# 02.net
KiCad netlist of a schematic drawn in Altium Designer
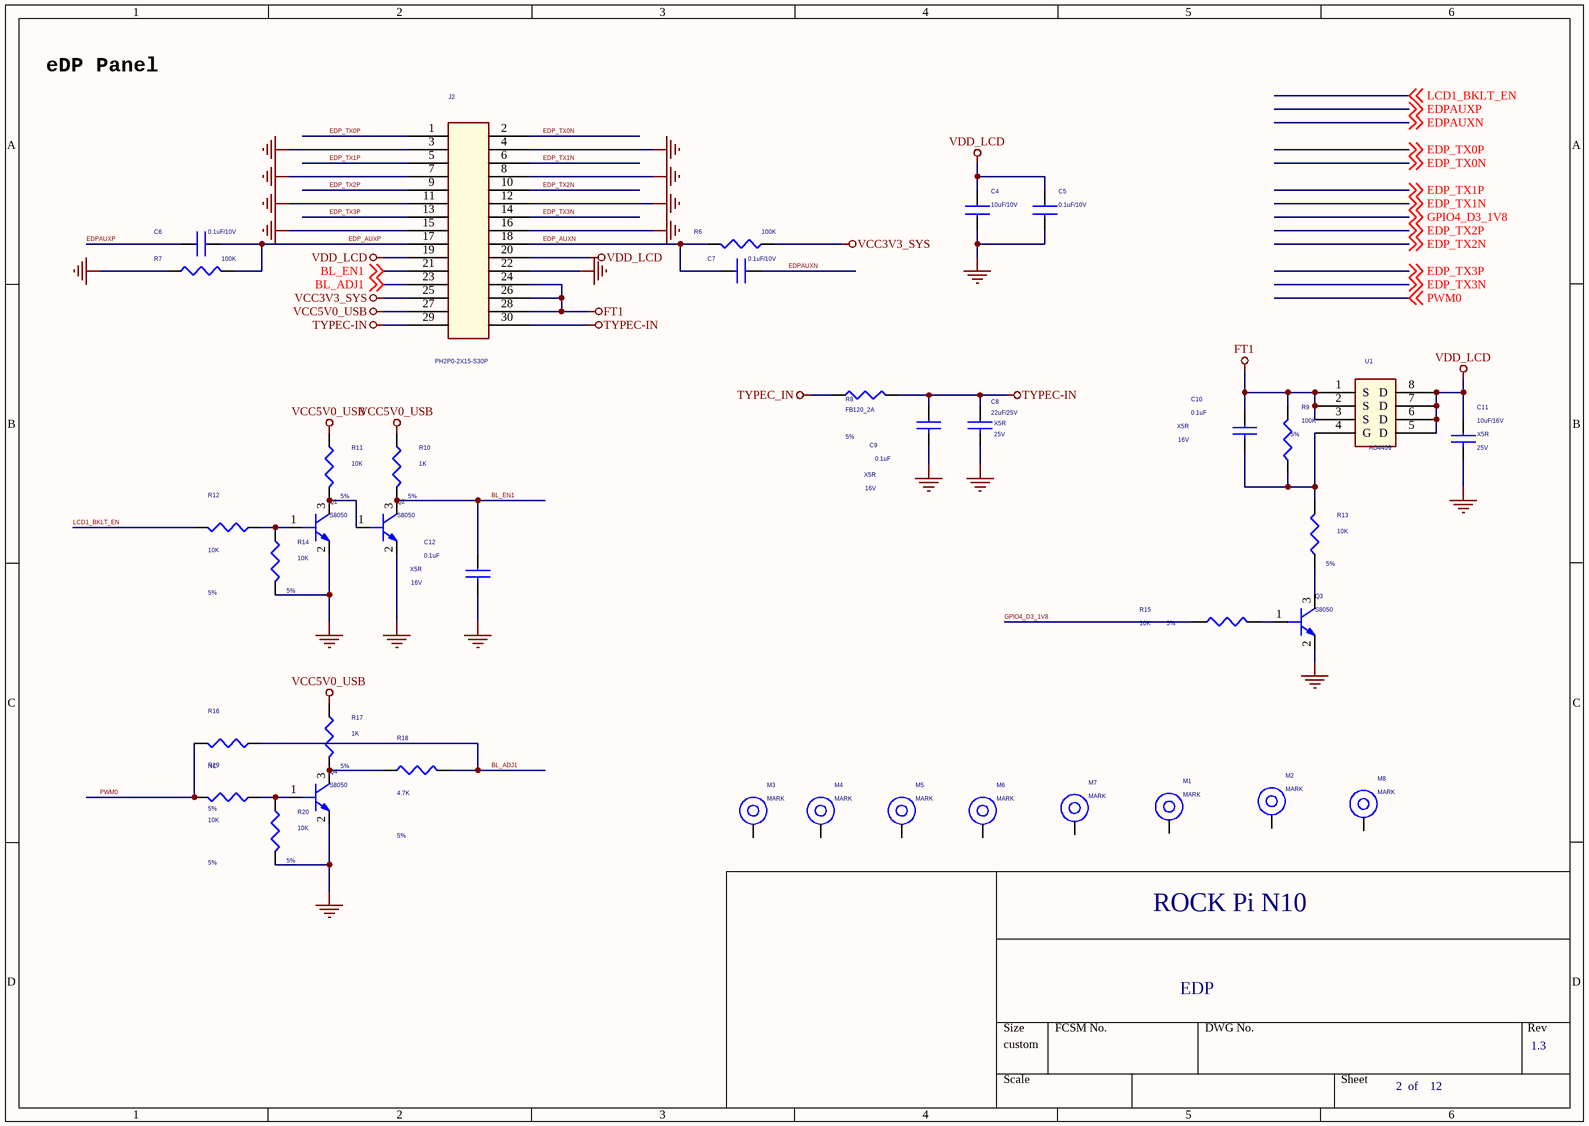
[diagram p0: 02.SchDoc]

(export (version "E")
  (design (tool "Eeschema 10.0.6"))
  (components
    (comp (ref "C4")
      (value "10uF/10V")
      (footprint "C0603")
      (description "CAP,MLCC,4.7uF,+/-10%,X5R,6.3V,SMD0603")
      (libsource (lib "*") (part "CAP NP_Dup4"))
    )
    (comp (ref "C5")
      (value "0.1uF/10V")
      (footprint "C0603")
      (description "CAP,MLCC,100nF,+/-10%,X7R,6.3V,SMD0402")
      (libsource (lib "*") (part "CAP NP_Dup4"))
    )
    (comp (ref "C6")
      (value "0.1uF/10V")
      (footprint "C0603")
      (description "CAP,MLCC,100nF,+/-10%,X7R,6.3V,SMD0402")
      (libsource (lib "*") (part "CAP NP_Dup4"))
    )
    (comp (ref "C7")
      (value "0.1uF/10V")
      (footprint "C0603")
      (description "CAP,MLCC,100nF,+/-10%,X7R,6.3V,SMD0402")
      (libsource (lib "*") (part "CAP NP_Dup4"))
    )
    (comp (ref "C8")
      (value "22uF/25V")
      (footprint "C0805")
      (description "cap,4.70uF,+/-10%,6.3V,X5R,C0603")
      (fields
        (field (name "DIELECTRIC") "X5R")
        (field (name "VOLTAGE") "25V")
        (field (name "MANUFACTURER") "TDK")
        (field (name "TOLERANCE") "10%")
        (field (name "CREATED BY") "JJJ")
      )
      (libsource (lib "*") (part "CAP NP_2"))
    )
    (comp (ref "C9")
      (value "0.1uF")
      (footprint "C0402")
      (description "cap,100.00nF,+/-10%,6.3V,X5R,C0402")
      (fields
        (field (name "DIELECTRIC") "X5R")
        (field (name "VOLTAGE") "16V")
        (field (name "MANUFACTURER") "TDK")
        (field (name "TOLERANCE") "10%")
        (field (name "CREATED BY") "JJJ")
      )
      (libsource (lib "*") (part "CAP NP_2"))
    )
    (comp (ref "C10")
      (value "0.1uF")
      (footprint "C0402")
      (description "cap,100.00nF,+/-10%,6.3V,X5R,C0402")
      (fields
        (field (name "DIELECTRIC") "X5R")
        (field (name "VOLTAGE") "16V")
        (field (name "TOLERANCE") "10%")
        (field (name "MANUFACTURER") "TDK")
        (field (name "CREATED BY") "JJJ")
      )
      (libsource (lib "*") (part "CAP NP_2"))
    )
    (comp (ref "C11")
      (value "10uF/16V")
      (footprint "C0805")
      (description "cap,4.70uF,+/-10%,6.3V,X5R,C0603")
      (fields
        (field (name "DIELECTRIC") "X5R")
        (field (name "VOLTAGE") "25V")
        (field (name "TOLERANCE") "10%")
        (field (name "MANUFACTURER") "TDK")
        (field (name "CREATED BY") "JJJ")
      )
      (libsource (lib "*") (part "CAP NP_2"))
    )
    (comp (ref "C12")
      (value "0.1uF")
      (footprint "C0402")
      (description "cap,100.00nF,+/-10%,6.3V,X5R,C0402")
      (fields
        (field (name "DIELECTRIC") "X5R")
        (field (name "VOLTAGE") "16V")
        (field (name "MANUFACTURER") "TDK")
        (field (name "TOLERANCE") "10%")
        (field (name "CREATED BY") "JJJ")
      )
      (libsource (lib "*") (part "CAP NP_2"))
    )
    (comp (ref "J2")
      (value "PH2P0-2X15-S30P")
      (footprint "PH2P0-2X15-S30P")
      (libsource (lib "*") (part "CON20A_2"))
    )
    (comp (ref "M1")
      (value "MARK")
      (footprint "MARK")
      (description "MARK Symble")
      (fields (field (name "CREATED BY") "CZD"))
      (libsource (lib "*") (part "MARK"))
    )
    (comp (ref "M2")
      (value "MARK")
      (footprint "MARK")
      (description "MARK Symble")
      (fields (field (name "CREATED BY") "CZD"))
      (libsource (lib "*") (part "MARK"))
    )
    (comp (ref "M3")
      (value "MARK")
      (footprint "MARK")
      (description "MARK Symble")
      (fields (field (name "CREATED BY") "CZD"))
      (libsource (lib "*") (part "MARK"))
    )
    (comp (ref "M4")
      (value "MARK")
      (footprint "MARK")
      (description "MARK Symble")
      (fields (field (name "CREATED BY") "CZD"))
      (libsource (lib "*") (part "MARK"))
    )
    (comp (ref "M5")
      (value "MARK")
      (footprint "MARK")
      (description "MARK Symble")
      (fields (field (name "CREATED BY") "CZD"))
      (libsource (lib "*") (part "MARK"))
    )
    (comp (ref "M6")
      (value "MARK")
      (footprint "MARK")
      (description "MARK Symble")
      (fields (field (name "CREATED BY") "CZD"))
      (libsource (lib "*") (part "MARK"))
    )
    (comp (ref "M7")
      (value "MARK")
      (footprint "MARK")
      (description "MARK Symble")
      (fields (field (name "CREATED BY") "CZD"))
      (libsource (lib "*") (part "MARK"))
    )
    (comp (ref "M8")
      (value "MARK")
      (footprint "MARK")
      (description "MARK Symble")
      (fields (field (name "CREATED BY") "CZD"))
      (libsource (lib "*") (part "MARK"))
    )
    (comp (ref "Q1")
      (value "S8050")
      (footprint "SOT_23")
      (description "S8050 SOT23")
      (fields (field (name "MANUFACTURER") "长电") (field (name "CREATED BY") "JJJ"))
      (libsource (lib "*") (part "NPN"))
    )
    (comp (ref "Q2")
      (value "S8050")
      (footprint "SOT_23")
      (description "S8050 SOT23")
      (fields (field (name "MANUFACTURER") "长电") (field (name "CREATED BY") "JJJ"))
      (libsource (lib "*") (part "NPN"))
    )
    (comp (ref "Q3")
      (value "S8050")
      (footprint "SOT23")
      (description "S8050 SOT23")
      (fields (field (name "MANUFACTURER") "长电") (field (name "CREATED BY") "JJJ"))
      (libsource (lib "*") (part "NPN"))
    )
    (comp (ref "Q4")
      (value "S8050")
      (footprint "SOT_23")
      (description "S8050 SOT23")
      (fields (field (name "MANUFACTURER") "长电") (field (name "CREATED BY") "JJJ"))
      (libsource (lib "*") (part "NPN"))
    )
    (comp (ref "R6") (value "100K") (footprint "R0402") (libsource (lib "*") (part "RESISTOR_1_Dup1")))
    (comp (ref "R7") (value "100K") (footprint "R0402") (libsource (lib "*") (part "RESISTOR_1_Dup1")))
    (comp (ref "R8")
      (value "FB120_2A")
      (footprint "R0402")
      (description "通用厚膜电阻,10K,+/-5%,R0402,1/16W.")
      (fields
        (field (name "TOLERANCE") "5%")
        (field (name "MANUFACTURER") "YAGEO")
        (field (name "CREATED BY") "YTL")
      )
      (libsource (lib "*") (part "RESISTOR_3"))
    )
    (comp (ref "R9")
      (value "100K")
      (footprint "R0402")
      (description "通用厚膜电阻,100K,+/-5%,R0402,1/16W.")
      (fields
        (field (name "TOLERANCE") "5%")
        (field (name "MANUFACTURER") "YAGEO")
        (field (name "CREATED BY") "YTL")
      )
      (libsource (lib "*") (part "RESISTOR_3"))
    )
    (comp (ref "R10")
      (value "1K")
      (footprint "R0402")
      (description "通用厚膜电阻,10K,+/-5%,R0402,1/16W.")
      (fields
        (field (name "TOLERANCE") "5%")
        (field (name "MANUFACTURER") "YAGEO")
        (field (name "CREATED BY") "YTL")
      )
      (libsource (lib "*") (part "RESISTOR_3"))
    )
    (comp (ref "R11")
      (value "10K")
      (footprint "R0402")
      (description "通用厚膜电阻,10K,+/-5%,R0402,1/16W.")
      (fields
        (field (name "TOLERANCE") "5%")
        (field (name "MANUFACTURER") "YAGEO")
        (field (name "CREATED BY") "YTL")
      )
      (libsource (lib "*") (part "RESISTOR_3"))
    )
    (comp (ref "R12")
      (value "10K")
      (footprint "R0402")
      (description "通用厚膜电阻,10K,+/-5%,R0402,1/16W.")
      (fields
        (field (name "TOLERANCE") "5%")
        (field (name "MANUFACTURER") "YAGEO")
        (field (name "CREATED BY") "YTL")
      )
      (libsource (lib "*") (part "RESISTOR_3"))
    )
    (comp (ref "R13")
      (value "10K")
      (footprint "R0402")
      (description "通用厚膜电阻,10K,+/-5%,R0402,1/16W.")
      (fields
        (field (name "TOLERANCE") "5%")
        (field (name "MANUFACTURER") "YAGEO")
        (field (name "CREATED BY") "YTL")
      )
      (libsource (lib "*") (part "RESISTOR_3"))
    )
    (comp (ref "R14")
      (value "10K")
      (footprint "R0402")
      (description "通用厚膜电阻,10K,+/-5%,R0402,1/16W.")
      (fields
        (field (name "TOLERANCE") "5%")
        (field (name "MANUFACTURER") "YAGEO")
        (field (name "CREATED BY") "YTL")
      )
      (libsource (lib "*") (part "RESISTOR_3"))
    )
    (comp (ref "R15")
      (value "10K")
      (footprint "R0402")
      (description "通用厚膜电阻,10K,+/-5%,R0402,1/16W.")
      (fields
        (field (name "TOLERANCE") "5%")
        (field (name "MANUFACTURER") "YAGEO")
        (field (name "CREATED BY") "YTL")
      )
      (libsource (lib "*") (part "RESISTOR_3"))
    )
    (comp (ref "R16")
      (value "NC")
      (footprint "R0402")
      (description "通用厚膜电阻,10K,+/-5%,R0402,1/16W.")
      (fields
        (field (name "TOLERANCE") "5%")
        (field (name "MANUFACTURER") "YAGEO")
        (field (name "CREATED BY") "YTL")
      )
      (libsource (lib "*") (part "RESISTOR_3"))
    )
    (comp (ref "R17")
      (value "1K")
      (footprint "R0402")
      (description "通用厚膜电阻,10K,+/-5%,R0402,1/16W.")
      (fields
        (field (name "TOLERANCE") "5%")
        (field (name "MANUFACTURER") "YAGEO")
        (field (name "CREATED BY") "YTL")
      )
      (libsource (lib "*") (part "RESISTOR_3"))
    )
    (comp (ref "R18")
      (value "4.7K")
      (footprint "R0402")
      (description "通用厚膜电阻,10K,+/-5%,R0402,1/16W.")
      (fields
        (field (name "TOLERANCE") "5%")
        (field (name "MANUFACTURER") "YAGEO")
        (field (name "CREATED BY") "YTL")
      )
      (libsource (lib "*") (part "RESISTOR_3"))
    )
    (comp (ref "R19")
      (value "10K")
      (footprint "R0402")
      (description "通用厚膜电阻,10K,+/-5%,R0402,1/16W.")
      (fields
        (field (name "TOLERANCE") "5%")
        (field (name "MANUFACTURER") "YAGEO")
        (field (name "CREATED BY") "YTL")
      )
      (libsource (lib "*") (part "RESISTOR_3"))
    )
    (comp (ref "R20")
      (value "10K")
      (footprint "R0402")
      (description "通用厚膜电阻,10K,+/-5%,R0402,1/16W.")
      (fields
        (field (name "TOLERANCE") "5%")
        (field (name "MANUFACTURER") "YAGEO")
        (field (name "CREATED BY") "YTL")
      )
      (libsource (lib "*") (part "RESISTOR_3"))
    )
    (comp (ref "U1") (value "AO4409") (footprint "SOP8-50-150") (libsource (lib "*") (part "AO4409_0")))
  )
  (nets
    (net (code "1") (name "/EDP_AUXN") (class "Default")
      (node (ref "C7") (pin "2") (pinfunction "2_2") (pintype "passive"))
      (node (ref "J2") (pin "18") (pinfunction "18_18") (pintype "passive"))
      (node (ref "R6") (pin "1") (pinfunction "1_1") (pintype "passive"))
    )
    (net (code "2") (name "/EDP_AUXP") (class "Default")
      (node (ref "C6") (pin "2") (pinfunction "2_2") (pintype "passive"))
      (node (ref "J2") (pin "17") (pinfunction "17_17") (pintype "passive"))
      (node (ref "R7") (pin "1") (pinfunction "1_1") (pintype "passive"))
    )
    (net (code "3") (name "BL_ADJ1") (class "Default")
      (node (ref "J2") (pin "23") (pinfunction "23_23") (pintype "passive"))
      (node (ref "R16") (pin "2") (pinfunction "2_2") (pintype "passive"))
      (node (ref "R18") (pin "1") (pinfunction "1_1") (pintype "passive"))
    )
    (net (code "4") (name "BL_EN1") (class "Default")
      (node (ref "C12") (pin "1") (pinfunction "1_1") (pintype "passive"))
      (node (ref "J2") (pin "21") (pinfunction "21_21") (pintype "passive"))
      (node (ref "Q2") (pin "3") (pinfunction "COLLECTOR_3") (pintype "passive"))
      (node (ref "R10") (pin "1") (pinfunction "1_1") (pintype "passive"))
    )
    (net (code "5") (name "EDPAUXN") (class "Default")
      (node (ref "C7") (pin "1") (pinfunction "1_1") (pintype "passive"))
    )
    (net (code "6") (name "EDPAUXP") (class "Default")
      (node (ref "C6") (pin "1") (pinfunction "1_1") (pintype "passive"))
    )
    (net (code "7") (name "EDP_TX0N") (class "Default")
      (node (ref "J2") (pin "2") (pinfunction "2_2") (pintype "passive"))
    )
    (net (code "8") (name "EDP_TX0P") (class "Default")
      (node (ref "J2") (pin "1") (pinfunction "1_1") (pintype "passive"))
    )
    (net (code "9") (name "EDP_TX1N") (class "Default")
      (node (ref "J2") (pin "6") (pinfunction "6_6") (pintype "passive"))
    )
    (net (code "10") (name "EDP_TX1P") (class "Default")
      (node (ref "J2") (pin "5") (pinfunction "5_5") (pintype "passive"))
    )
    (net (code "11") (name "EDP_TX2N") (class "Default")
      (node (ref "J2") (pin "10") (pinfunction "10_10") (pintype "passive"))
    )
    (net (code "12") (name "EDP_TX2P") (class "Default")
      (node (ref "J2") (pin "9") (pinfunction "9_9") (pintype "passive"))
    )
    (net (code "13") (name "EDP_TX3N") (class "Default")
      (node (ref "J2") (pin "14") (pinfunction "14_14") (pintype "passive"))
    )
    (net (code "14") (name "EDP_TX3P") (class "Default")
      (node (ref "J2") (pin "13") (pinfunction "13_13") (pintype "passive"))
    )
    (net (code "15") (name "FT1") (class "Default")
      (node (ref "C10") (pin "1") (pinfunction "1_1") (pintype "passive"))
      (node (ref "J2") (pin "24") (pinfunction "24_24") (pintype "passive"))
      (node (ref "J2") (pin "26") (pinfunction "26_26") (pintype "passive"))
      (node (ref "J2") (pin "28") (pinfunction "28_28") (pintype "passive"))
      (node (ref "R9") (pin "1") (pinfunction "1_1") (pintype "passive"))
      (node (ref "U1") (pin "1") (pinfunction "S_1") (pintype "passive"))
      (node (ref "U1") (pin "2") (pinfunction "S_2") (pintype "passive"))
      (node (ref "U1") (pin "3") (pinfunction "S_3") (pintype "passive"))
    )
    (net (code "16") (name "GND") (class "Default")
      (node (ref "C11") (pin "2") (pinfunction "2_2") (pintype "passive"))
      (node (ref "C12") (pin "2") (pinfunction "2_2") (pintype "passive"))
      (node (ref "C4") (pin "2") (pinfunction "2_2") (pintype "passive"))
      (node (ref "C5") (pin "2") (pinfunction "2_2") (pintype "passive"))
      (node (ref "C8") (pin "2") (pinfunction "2_2") (pintype "passive"))
      (node (ref "C9") (pin "2") (pinfunction "2_2") (pintype "passive"))
      (node (ref "J2") (pin "11") (pinfunction "11_11") (pintype "passive"))
      (node (ref "J2") (pin "12") (pinfunction "12_12") (pintype "passive"))
      (node (ref "J2") (pin "15") (pinfunction "15_15") (pintype "passive"))
      (node (ref "J2") (pin "16") (pinfunction "16_16") (pintype "passive"))
      (node (ref "J2") (pin "22") (pinfunction "22_22") (pintype "passive"))
      (node (ref "J2") (pin "3") (pinfunction "3_3") (pintype "passive"))
      (node (ref "J2") (pin "4") (pinfunction "4_4") (pintype "passive"))
      (node (ref "J2") (pin "7") (pinfunction "7_7") (pintype "passive"))
      (node (ref "J2") (pin "8") (pinfunction "8_8") (pintype "passive"))
      (node (ref "Q1") (pin "2") (pinfunction "EMITTER_2") (pintype "passive"))
      (node (ref "Q2") (pin "2") (pinfunction "EMITTER_2") (pintype "passive"))
      (node (ref "Q3") (pin "2") (pinfunction "EMITTER_2") (pintype "passive"))
      (node (ref "Q4") (pin "2") (pinfunction "EMITTER_2") (pintype "passive"))
      (node (ref "R14") (pin "1") (pinfunction "1_1") (pintype "passive"))
      (node (ref "R20") (pin "1") (pinfunction "1_1") (pintype "passive"))
      (node (ref "R7") (pin "2") (pinfunction "2_2") (pintype "passive"))
    )
    (net (code "17") (name "GPIO4_D3_1V8") (class "Default")
      (node (ref "R15") (pin "1") (pinfunction "1_1") (pintype "passive"))
    )
    (net (code "18") (name "LCD1_BKLT_EN") (class "Default")
      (node (ref "R12") (pin "1") (pinfunction "1_1") (pintype "passive"))
    )
    (net (code "19") (name "Net-(Q1-BASE)") (class "Default")
      (node (ref "Q1") (pin "1") (pinfunction "BASE_1") (pintype "passive"))
      (node (ref "R12") (pin "2") (pinfunction "2_2") (pintype "passive"))
      (node (ref "R14") (pin "2") (pinfunction "2_2") (pintype "passive"))
    )
    (net (code "20") (name "Net-(Q1-COLLECTOR)") (class "Default")
      (node (ref "Q1") (pin "3") (pinfunction "COLLECTOR_3") (pintype "passive"))
      (node (ref "Q2") (pin "1") (pinfunction "BASE_1") (pintype "passive"))
      (node (ref "R11") (pin "1") (pinfunction "1_1") (pintype "passive"))
    )
    (net (code "21") (name "Net-(Q3-BASE)") (class "Default")
      (node (ref "Q3") (pin "1") (pinfunction "BASE_1") (pintype "passive"))
      (node (ref "R15") (pin "2") (pinfunction "2_2") (pintype "passive"))
    )
    (net (code "22") (name "Net-(Q3-COLLECTOR)") (class "Default")
      (node (ref "Q3") (pin "3") (pinfunction "COLLECTOR_3") (pintype "passive"))
      (node (ref "R13") (pin "2") (pinfunction "2_2") (pintype "passive"))
    )
    (net (code "23") (name "Net-(Q4-BASE)") (class "Default")
      (node (ref "Q4") (pin "1") (pinfunction "BASE_1") (pintype "passive"))
      (node (ref "R19") (pin "2") (pinfunction "2_2") (pintype "passive"))
      (node (ref "R20") (pin "2") (pinfunction "2_2") (pintype "passive"))
    )
    (net (code "24") (name "Net-(Q4-COLLECTOR)") (class "Default")
      (node (ref "Q4") (pin "3") (pinfunction "COLLECTOR_3") (pintype "passive"))
      (node (ref "R17") (pin "1") (pinfunction "1_1") (pintype "passive"))
      (node (ref "R18") (pin "2") (pinfunction "2_2") (pintype "passive"))
    )
    (net (code "25") (name "Net-(U1-G)") (class "Default")
      (node (ref "C10") (pin "2") (pinfunction "2_2") (pintype "passive"))
      (node (ref "R13") (pin "1") (pinfunction "1_1") (pintype "passive"))
      (node (ref "R9") (pin "2") (pinfunction "2_2") (pintype "passive"))
      (node (ref "U1") (pin "4") (pinfunction "G_4") (pintype "passive"))
    )
    (net (code "26") (name "PWM0") (class "Default")
      (node (ref "R16") (pin "1") (pinfunction "1_1") (pintype "passive"))
      (node (ref "R19") (pin "1") (pinfunction "1_1") (pintype "passive"))
    )
    (net (code "27") (name "TYPEC-IN") (class "Default")
      (node (ref "C8") (pin "1") (pinfunction "1_1") (pintype "passive"))
      (node (ref "C9") (pin "1") (pinfunction "1_1") (pintype "passive"))
      (node (ref "J2") (pin "29") (pinfunction "29_29") (pintype "passive"))
      (node (ref "J2") (pin "30") (pinfunction "30_30") (pintype "passive"))
      (node (ref "R8") (pin "2") (pinfunction "2_2") (pintype "passive"))
    )
    (net (code "28") (name "TYPEC_IN") (class "Default")
      (node (ref "R8") (pin "1") (pinfunction "1_1") (pintype "passive"))
    )
    (net (code "29") (name "VCC3V3_SYS") (class "Default")
      (node (ref "J2") (pin "25") (pinfunction "25_25") (pintype "passive"))
      (node (ref "R6") (pin "2") (pinfunction "2_2") (pintype "passive"))
    )
    (net (code "30") (name "VCC5V0_USB") (class "Default")
      (node (ref "J2") (pin "27") (pinfunction "27_27") (pintype "passive"))
      (node (ref "R10") (pin "2") (pinfunction "2_2") (pintype "passive"))
      (node (ref "R11") (pin "2") (pinfunction "2_2") (pintype "passive"))
      (node (ref "R17") (pin "2") (pinfunction "2_2") (pintype "passive"))
    )
    (net (code "31") (name "VDD_LCD") (class "Default")
      (node (ref "C11") (pin "1") (pinfunction "1_1") (pintype "passive"))
      (node (ref "C4") (pin "1") (pinfunction "1_1") (pintype "passive"))
      (node (ref "C5") (pin "1") (pinfunction "1_1") (pintype "passive"))
      (node (ref "J2") (pin "19") (pinfunction "19_19") (pintype "passive"))
      (node (ref "J2") (pin "20") (pinfunction "20_20") (pintype "passive"))
      (node (ref "U1") (pin "5") (pinfunction "D_5") (pintype "passive"))
      (node (ref "U1") (pin "6") (pinfunction "D_6") (pintype "passive"))
      (node (ref "U1") (pin "7") (pinfunction "D_7") (pintype "passive"))
      (node (ref "U1") (pin "8") (pinfunction "D_8") (pintype "passive"))
    )
    (net (code "32") (name "unconnected-(M1-Pad1)") (class "Default")
      (node (ref "M1") (pin "1") (pinfunction "1_1") (pintype "passive"))
    )
    (net (code "33") (name "unconnected-(M2-Pad1)") (class "Default")
      (node (ref "M2") (pin "1") (pinfunction "1_1") (pintype "passive"))
    )
    (net (code "34") (name "unconnected-(M3-Pad1)") (class "Default")
      (node (ref "M3") (pin "1") (pinfunction "1_1") (pintype "passive"))
    )
    (net (code "35") (name "unconnected-(M4-Pad1)") (class "Default")
      (node (ref "M4") (pin "1") (pinfunction "1_1") (pintype "passive"))
    )
    (net (code "36") (name "unconnected-(M5-Pad1)") (class "Default")
      (node (ref "M5") (pin "1") (pinfunction "1_1") (pintype "passive"))
    )
    (net (code "37") (name "unconnected-(M6-Pad1)") (class "Default")
      (node (ref "M6") (pin "1") (pinfunction "1_1") (pintype "passive"))
    )
    (net (code "38") (name "unconnected-(M7-Pad1)") (class "Default")
      (node (ref "M7") (pin "1") (pinfunction "1_1") (pintype "passive"))
    )
    (net (code "39") (name "unconnected-(M8-Pad1)") (class "Default")
      (node (ref "M8") (pin "1") (pinfunction "1_1") (pintype "passive"))
    )
  )
)
